# MicroBoard030603.net
KiCad netlist of a schematic drawn in Altium Designer
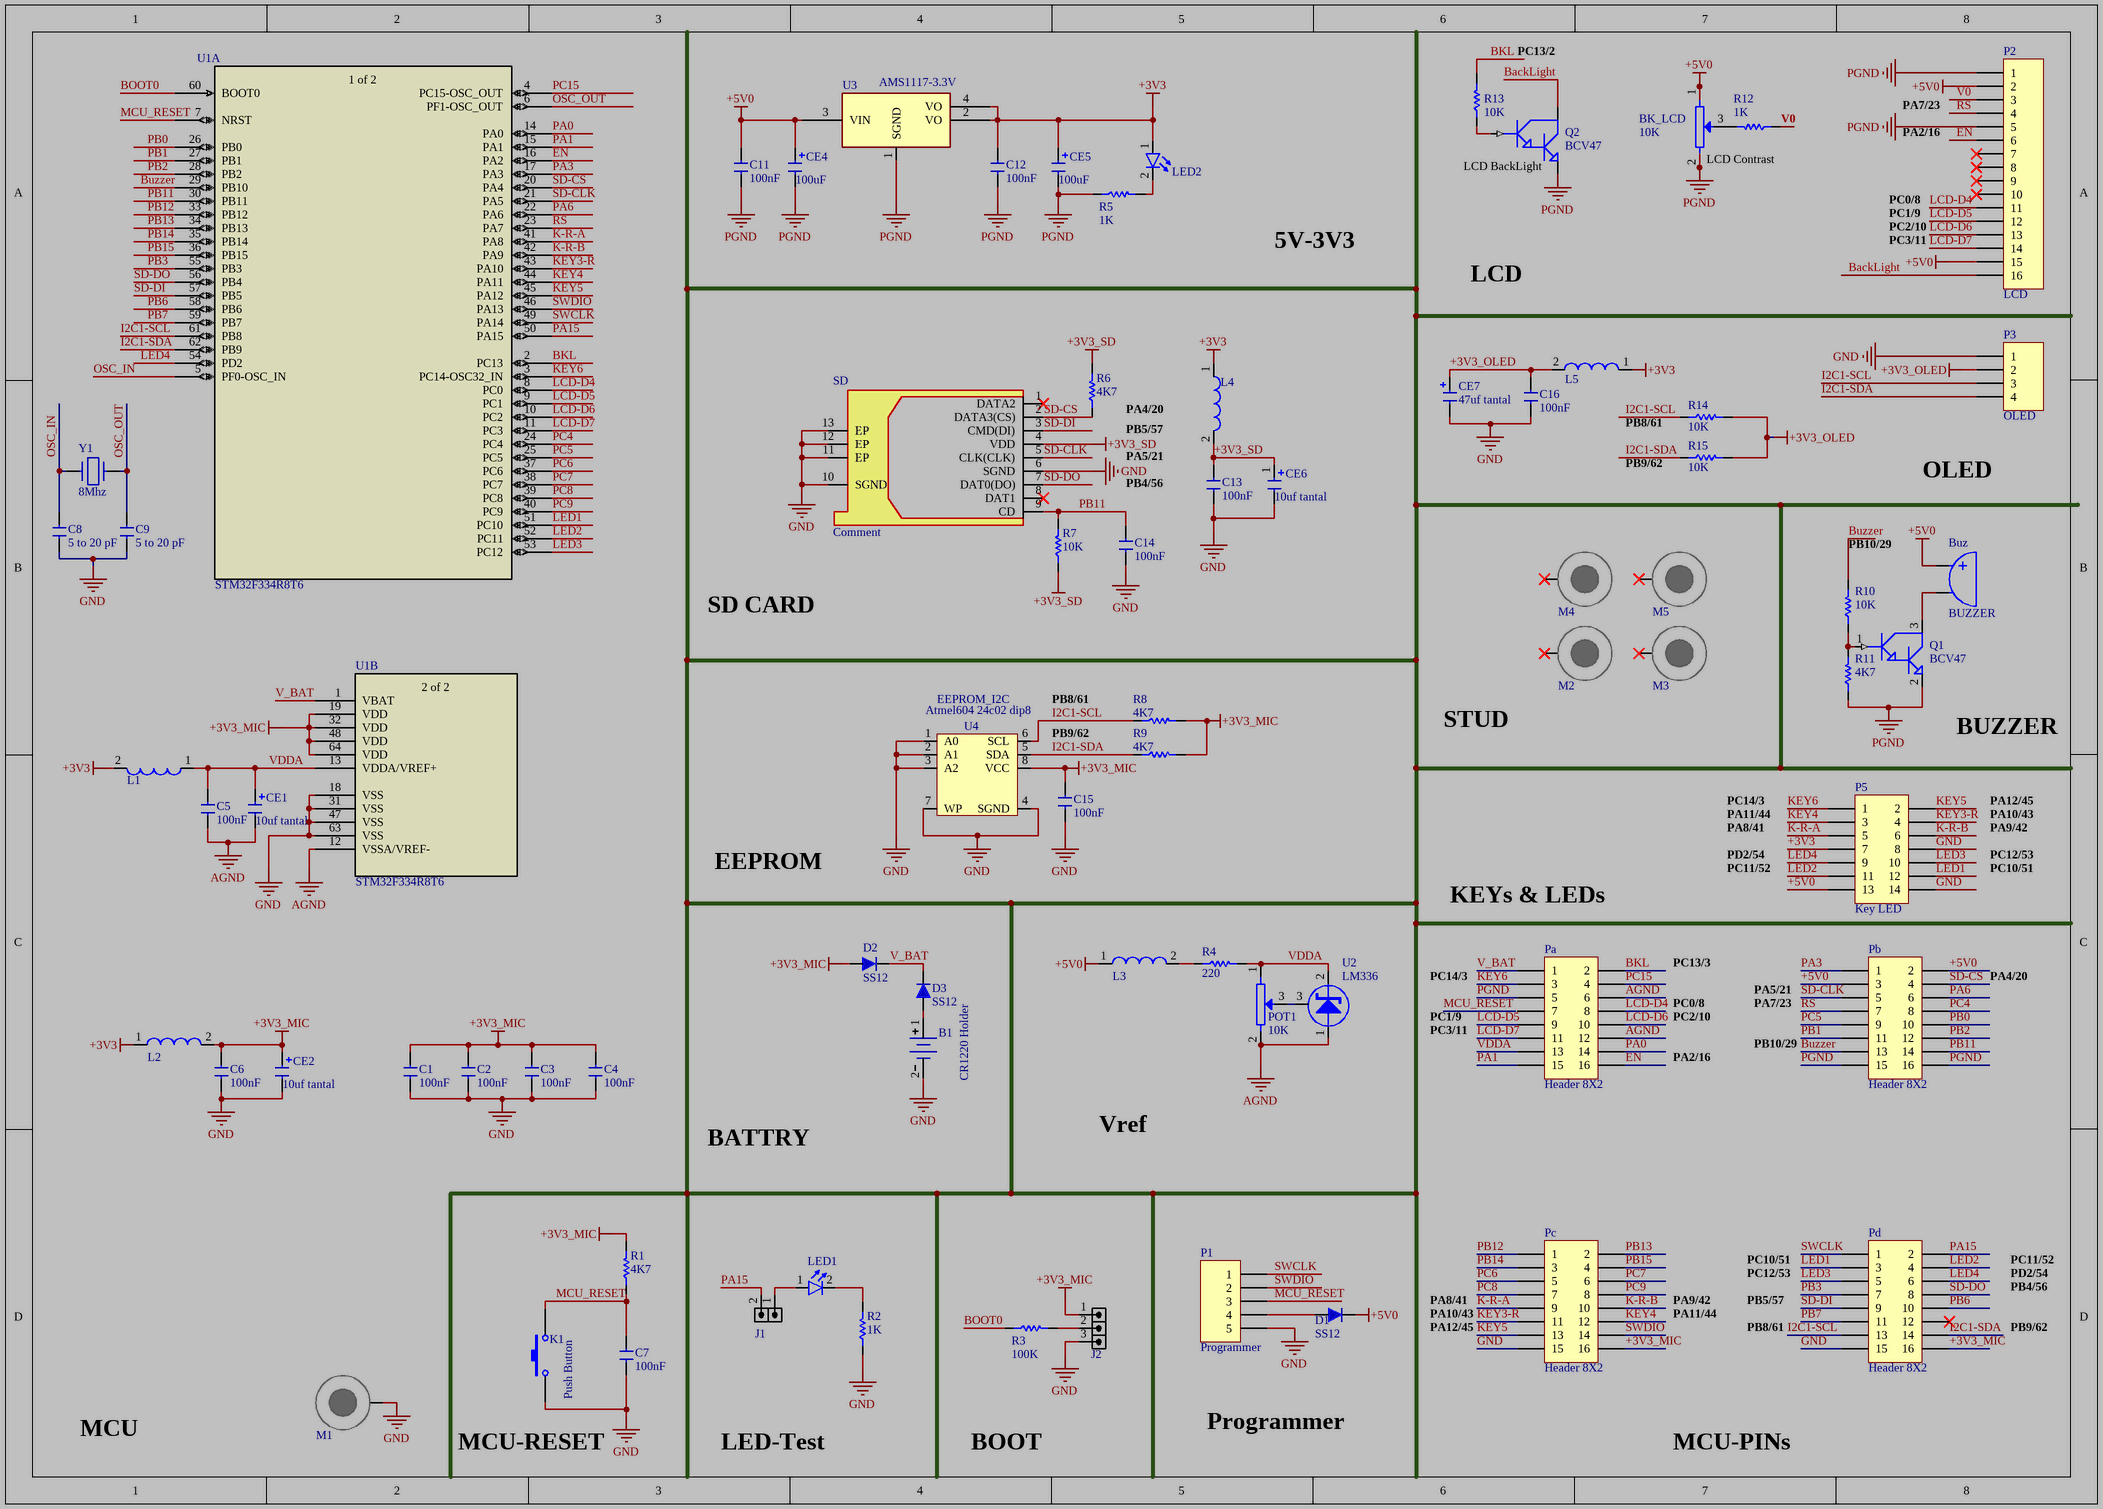
[diagram p0: MicroBoard030603.SchDoc]

(export (version "E")
  (design (tool "Eeschema 10.0.6"))
  (components
    (comp (ref "B1")
      (value "CR1220 Holder")
      (footprint "BAT S")
      (libsource (lib "DotexGroup_LIB") (part "Battry Backup"))
    )
    (comp (ref "BK_LCD")
      (value "10K")
      (footprint "POT-Blue")
      (libsource (lib "1402 Schlib 2020") (part "POT2"))
    )
    (comp (ref "Buz")
      (value "BUZZER")
      (footprint "BUZ")
      (libsource (lib "Previous Backup of Device") (part "BUZZER"))
    )
    (comp (ref "C1")
      (value "Comment")
      (footprint "SMD_CAP_1206.")
      (fields (field (name "ALTIUM_UNNAMED_1") "100nF"))
      (libsource (lib "DotexGroup_LIB") (part "Capacitor SMD"))
    )
    (comp (ref "C2")
      (value "Comment")
      (footprint "SMD_CAP_1206.")
      (fields (field (name "ALTIUM_UNNAMED_1") "100nF"))
      (libsource (lib "DotexGroup_LIB") (part "Capacitor SMD"))
    )
    (comp (ref "C3")
      (value "Comment")
      (footprint "SMD_CAP_1206.")
      (fields (field (name "ALTIUM_UNNAMED_1") "100nF"))
      (libsource (lib "DotexGroup_LIB") (part "Capacitor SMD"))
    )
    (comp (ref "C4")
      (value "Comment")
      (footprint "SMD_CAP_1206.")
      (fields (field (name "ALTIUM_UNNAMED_1") "100nF"))
      (libsource (lib "DotexGroup_LIB") (part "Capacitor SMD"))
    )
    (comp (ref "C5")
      (value "Comment")
      (footprint "SMD_CAP_1206.")
      (fields (field (name "ALTIUM_UNNAMED_1") "100nF"))
      (libsource (lib "DotexGroup_LIB") (part "Capacitor SMD"))
    )
    (comp (ref "C6")
      (value "Comment")
      (footprint "SMD_CAP_1206.")
      (fields (field (name "ALTIUM_UNNAMED_1") "100nF"))
      (libsource (lib "DotexGroup_LIB") (part "Capacitor SMD"))
    )
    (comp (ref "C7")
      (value "Comment")
      (footprint "SMD_CAP_1206.")
      (fields (field (name "ALTIUM_UNNAMED_1") "100nF"))
      (libsource (lib "DotexGroup_LIB") (part "Capacitor SMD"))
    )
    (comp (ref "C8")
      (value "Comment")
      (footprint "CAP 1206 (3216X15L)")
      (fields (field (name "ALTIUM_UNNAMED_1") "5 to 20 pF"))
      (libsource (lib "DotexGroup_LIB") (part "Capacitor SMD"))
    )
    (comp (ref "C9")
      (value "Comment")
      (footprint "CAP 1206 (3216X15L)")
      (fields (field (name "ALTIUM_UNNAMED_1") "5 to 20 pF"))
      (libsource (lib "DotexGroup_LIB") (part "Capacitor SMD"))
    )
    (comp (ref "C11")
      (value "Comment")
      (footprint "SMD_CAP_1206.")
      (fields (field (name "ALTIUM_UNNAMED_1") "100nF"))
      (libsource (lib "DotexGroup_LIB") (part "Capacitor SMD"))
    )
    (comp (ref "C12")
      (value "Comment")
      (footprint "SMD_CAP_1206.")
      (fields (field (name "ALTIUM_UNNAMED_1") "100nF"))
      (libsource (lib "DotexGroup_LIB") (part "Capacitor SMD"))
    )
    (comp (ref "C13")
      (value "Comment")
      (footprint "SMD_CAP_1206.")
      (fields (field (name "ALTIUM_UNNAMED_1") "100nF"))
      (libsource (lib "DotexGroup_LIB") (part "Capacitor SMD"))
    )
    (comp (ref "C14")
      (value "Comment")
      (footprint "SMD_CAP_1206.")
      (fields (field (name "ALTIUM_UNNAMED_1") "100nF"))
      (libsource (lib "DotexGroup_LIB") (part "Capacitor SMD"))
    )
    (comp (ref "C15")
      (value "Comment")
      (footprint "SMD_CAP_1206.")
      (fields (field (name "ALTIUM_UNNAMED_1") "100nF"))
      (libsource (lib "DotexGroup_LIB") (part "Capacitor SMD"))
    )
    (comp (ref "C16")
      (value "Comment")
      (footprint "SMD_CAP_1206.")
      (fields (field (name "ALTIUM_UNNAMED_1") "100nF"))
      (libsource (lib "DotexGroup_LIB") (part "Capacitor SMD"))
    )
    (comp (ref "CE1")
      (value "10uf tantal")
      (footprint "cap-e-2")
      (libsource (lib "DotexGroup_LIB") (part "Capacitor Tantalium"))
    )
    (comp (ref "CE2")
      (value "10uf tantal")
      (footprint "cap-e-2")
      (libsource (lib "DotexGroup_LIB") (part "Capacitor Tantalium"))
    )
    (comp (ref "CE4")
      (value "100uF")
      (footprint "cap-e-4")
      (libsource (lib "DotexGroup_LIB") (part "Capacitor Tantalium"))
    )
    (comp (ref "CE5")
      (value "100uF")
      (footprint "cap-e-4")
      (libsource (lib "DotexGroup_LIB") (part "Capacitor Tantalium"))
    )
    (comp (ref "CE6")
      (value "10uf tantal")
      (footprint "cap-e-2")
      (libsource (lib "") (part "Capacitor Tantalium_1"))
    )
    (comp (ref "CE7")
      (value "47uf tantal")
      (footprint "CAP-E-3")
      (libsource (lib "DotexGroup_LIB") (part "Capacitor Tantalium"))
    )
    (comp (ref "D1")
      (value "SS12")
      (footprint "Diode SMA-M")
      (libsource (lib "DotexGroup_LIB") (part "1N4001"))
    )
    (comp (ref "D2")
      (value "SS12")
      (footprint "Diode SMA-M")
      (libsource (lib "DotexGroup_LIB") (part "1N4001"))
    )
    (comp (ref "D3")
      (value "SS12")
      (footprint "Diode SMA-M")
      (libsource (lib "DotexGroup_LIB") (part "1N4001"))
    )
    (comp (ref "J1")
      (value "HDRM2")
      (footprint "HDR1X2")
      (description "CONN, HEADER, Male, pitch: 2.54mm, 2POS")
      (libsource (lib "conn_header") (part "HDR_M_1X2"))
    )
    (comp (ref "J2")
      (value "HDRM3")
      (footprint "HDR1X3")
      (description "CONN, HEADER, Male, pitch: 2.54mm, 3POS")
      (libsource (lib "conn_header") (part "HDR_M_1X3"))
    )
    (comp (ref "K1")
      (value "Push Button")
      (footprint "SW PB SMD")
      (libsource (lib "DotexGroup_LIB") (part "Push Kay"))
    )
    (comp (ref "L1")
      (value "Comment")
      (footprint "INDC4532")
      (libsource (lib "DotexGroup_LIB") (part "Ferrit Bead"))
    )
    (comp (ref "L2")
      (value "Comment")
      (footprint "L RES")
      (libsource (lib "DotexGroup_LIB") (part "Ferrit Bead"))
    )
    (comp (ref "L3")
      (value "Comment")
      (footprint "L RES")
      (libsource (lib "DotexGroup_LIB") (part "Ferrit Bead"))
    )
    (comp (ref "L4")
      (value "Comment")
      (footprint "L RES")
      (libsource (lib "DotexGroup_LIB") (part "Ferrit Bead"))
    )
    (comp (ref "L5") (value "Comment") (footprint "L RES") (libsource (lib "") (part "Ferrit Bead_1")))
    (comp (ref "LED1")
      (value "HB")
      (footprint "LED_SMD_1206")
      (description "LED")
      (fields (field (name "DESIGNER") "Saeid Jorablo"))
      (libsource (lib "3D") (part "LED"))
    )
    (comp (ref "LED2")
      (value "HB")
      (footprint "LED_SMD_1206")
      (description "LED")
      (fields (field (name "DESIGNER") "Saeid Jorablo"))
      (libsource (lib "3D") (part "LED"))
    )
    (comp (ref "M1")
      (value "Comment")
      (footprint "Stud-hole")
      (description "SCREW mouting, M1.6, 1.6mm diameter and 3.2mm PanHead")
      (libsource (lib "DotexGroup_LIB") (part "SCMH_M1P6"))
    )
    (comp (ref "M2")
      (value "Comment")
      (footprint "Stud-hole")
      (description "SCREW mouting, M1.6, 1.6mm diameter and 3.2mm PanHead")
      (libsource (lib "DotexGroup_LIB") (part "SCMH_M1P6"))
    )
    (comp (ref "M3")
      (value "Comment")
      (footprint "Stud-hole")
      (description "SCREW mouting, M1.6, 1.6mm diameter and 3.2mm PanHead")
      (libsource (lib "DotexGroup_LIB") (part "SCMH_M1P6"))
    )
    (comp (ref "M4")
      (value "Comment")
      (footprint "Stud-hole")
      (description "SCREW mouting, M1.6, 1.6mm diameter and 3.2mm PanHead")
      (libsource (lib "DotexGroup_LIB") (part "SCMH_M1P6"))
    )
    (comp (ref "M5")
      (value "Comment")
      (footprint "Stud-hole")
      (description "SCREW mouting, M1.6, 1.6mm diameter and 3.2mm PanHead")
      (libsource (lib "DotexGroup_LIB") (part "SCMH_M1P6"))
    )
    (comp (ref "P1")
      (value "Programmer")
      (footprint "SIP 5 right")
      (description "Header, 5-Pin")
      (fields (field (name "PUBLISHER") "Altium Limited"))
      (libsource (lib "Miscellaneous Connectors") (part "Header 5"))
    )
    (comp (ref "P2")
      (value "LCD")
      (footprint "HDR1X16")
      (description "Header, 16-Pin")
      (fields (field (name "PUBLISHER") "Altium Limited"))
      (libsource (lib "Miscellaneous Connectors") (part "Header 16"))
    )
    (comp (ref "P3")
      (value "OLED")
      (footprint "sip 4 right")
      (description "Header, 4-Pin")
      (fields (field (name "PUBLISHER") "Altium Limited"))
      (libsource (lib "Miscellaneous Connectors") (part "Header 4"))
    )
    (comp (ref "P5")
      (value "Key LED")
      (footprint "IDC14 r lock")
      (description "Header, 7-Pin, Dual row")
      (fields (field (name "PUBLISHER") "Altium Limited"))
      (libsource (lib "Miscellaneous Connectors") (part "Header 7X2"))
    )
    (comp (ref "Pa")
      (value "Header 8X2")
      (footprint "HDR2X8")
      (description "Header, 8-Pin, Dual row")
      (fields (field (name "PUBLISHER") "Altium Limited"))
      (libsource (lib "Miscellaneous Connectors") (part "Header 8X2"))
    )
    (comp (ref "Pb")
      (value "Header 8X2")
      (footprint "HDR2X8")
      (description "Header, 8-Pin, Dual row")
      (fields (field (name "PUBLISHER") "Altium Limited"))
      (libsource (lib "Miscellaneous Connectors") (part "Header 8X2"))
    )
    (comp (ref "Pc")
      (value "Header 8X2")
      (footprint "HDR2X8")
      (description "Header, 8-Pin, Dual row")
      (fields (field (name "PUBLISHER") "Altium Limited"))
      (libsource (lib "Miscellaneous Connectors") (part "Header 8X2"))
    )
    (comp (ref "Pd")
      (value "Header 8X2")
      (footprint "HDR2X8")
      (description "Header, 8-Pin, Dual row")
      (fields (field (name "PUBLISHER") "Altium Limited"))
      (libsource (lib "Miscellaneous Connectors") (part "Header 8X2"))
    )
    (comp (ref "POT1")
      (value "10K")
      (footprint "pot multi turn")
      (libsource (lib "1402 Schlib 2020") (part "POT2"))
    )
    (comp (ref "Q1") (value "BCV47") (footprint "SOT23_M") (libsource (lib "") (part "NPN DAR_1")))
    (comp (ref "Q2") (value "BCV47") (footprint "SOT23_M") (libsource (lib "MyAltiumLib") (part "NPN DAR")))
    (comp (ref "R1")
      (value "4K7")
      (footprint "RES_1206")
      (description "Resistor")
      (fields (field (name "TOLERANCE") "5%") (field (name "POWER") "1/8 W"))
      (libsource (lib "My Library") (part "Resistor"))
    )
    (comp (ref "R2")
      (value "1K")
      (footprint "RES_1206")
      (description "Resistor")
      (fields (field (name "TOLERANCE") "5%") (field (name "POWER") "1/8 W"))
      (libsource (lib "My Library") (part "Resistor"))
    )
    (comp (ref "R3")
      (value "100K")
      (footprint "RES_1206")
      (description "Resistor")
      (fields (field (name "TOLERANCE") "5%") (field (name "POWER") "1/8 W"))
      (libsource (lib "My Library") (part "Resistor"))
    )
    (comp (ref "R4")
      (value "220")
      (footprint "RES_1206")
      (description "Resistor")
      (fields (field (name "TOLERANCE") "5%") (field (name "POWER") "1/8 W"))
      (libsource (lib "My Library") (part "Resistor"))
    )
    (comp (ref "R5")
      (value "1K")
      (footprint "RES_1206")
      (description "Resistor")
      (fields (field (name "TOLERANCE") "5%") (field (name "POWER") "1/8 W"))
      (libsource (lib "My Library") (part "Resistor"))
    )
    (comp (ref "R6")
      (value "4K7")
      (footprint "RES_1206")
      (description "Resistor")
      (fields (field (name "TOLERANCE") "5%") (field (name "POWER") "1/8 W"))
      (libsource (lib "My Library") (part "Resistor"))
    )
    (comp (ref "R7")
      (value "10K")
      (footprint "RES_1206")
      (description "Resistor")
      (fields (field (name "TOLERANCE") "5%") (field (name "POWER") "1/8 W"))
      (libsource (lib "My Library") (part "Resistor"))
    )
    (comp (ref "R8")
      (value "4K7")
      (footprint "RES_1206")
      (description "Resistor")
      (fields (field (name "TOLERANCE") "5%") (field (name "POWER") "1/8 W"))
      (libsource (lib "My Library") (part "Resistor"))
    )
    (comp (ref "R9")
      (value "4K7")
      (footprint "RES_1206")
      (description "Resistor")
      (fields (field (name "TOLERANCE") "5%") (field (name "POWER") "1/8 W"))
      (libsource (lib "My Library") (part "Resistor"))
    )
    (comp (ref "R10")
      (value "10K")
      (footprint "RES_1206")
      (description "Resistor")
      (fields (field (name "TOLERANCE") "5%") (field (name "POWER") "1/8 W"))
      (libsource (lib "My Library") (part "Resistor"))
    )
    (comp (ref "R11")
      (value "4K7")
      (footprint "RES_1206")
      (description "Resistor")
      (fields (field (name "TOLERANCE") "5%") (field (name "POWER") "1/8 W"))
      (libsource (lib "My Library") (part "Resistor"))
    )
    (comp (ref "R12")
      (value "1K")
      (footprint "RES_1206")
      (description "Resistor")
      (fields (field (name "TOLERANCE") "5%") (field (name "POWER") "1/8 W"))
      (libsource (lib "My Library") (part "Resistor"))
    )
    (comp (ref "R13")
      (value "10K")
      (footprint "RES_1206")
      (description "Resistor")
      (fields (field (name "TOLERANCE") "5%") (field (name "POWER") "1/8 W"))
      (libsource (lib "My Library") (part "Resistor"))
    )
    (comp (ref "R14")
      (value "10K")
      (footprint "RES_1206")
      (description "Resistor")
      (fields (field (name "TOLERANCE") "5%") (field (name "POWER") "1/8 W"))
      (libsource (lib "My Library") (part "Resistor"))
    )
    (comp (ref "R15")
      (value "10K")
      (footprint "RES_1206")
      (description "Resistor")
      (fields (field (name "TOLERANCE") "5%") (field (name "POWER") "1/8 W"))
      (libsource (lib "My Library") (part "Resistor"))
    )
    (comp (ref "SD")
      (value "Comment")
      (footprint "Micro sd csrd")
      (libsource (lib "DotexGroup_LIB") (part "Micro SD Card"))
    )
    (comp (ref "U1")
      (value "STM32F334R8T6")
      (footprint "STM32F334R8T6")
      (description "No Description Available")
      (fields (field (name "COPYRIGHT") "Copyright (C) 2023 Ultra Librarian. All rights reserved."))
      (libsource (lib "STM32F334R8T6") (part "STM32F334R8T6"))
    )
    (comp (ref "U2") (value "LM336") (footprint "LM336") (libsource (lib "MyAltiumLib") (part "LM336")))
    (comp (ref "U3")
      (value "AMS1117-3.3V")
      (footprint "MP04A_M")
      (description "REG, Linear, LDO1V, 0.8A, SOT-223")
      (fields
        (field (name "MANF_P#") "LD1117, LM1117, AMS1117, TLV1117, REG1117, NCP1117, LT1117, SPX1117")
        (field (name "MANF") "TI, ON, ST")
      )
      (libsource (lib "DotexGroup_LIB") (part "VREG_1117_SOT223"))
    )
    (comp (ref "U4")
      (value "EEPROM_I2C")
      (footprint "dip8")
      (libsource (lib "DotexGroup_LIB") (part "AT24C128"))
    )
    (comp (ref "Y1")
      (value "8Mhz")
      (footprint "Crystal SMD")
      (libsource (lib "DotexGroup_LIB") (part "Xtal"))
    )
  )
  (nets
    (net (code "1") (name "+3V3") (class "Default")
      (node (ref "C12") (pin "2") (pintype "passive"))
      (node (ref "CE5") (pin "1") (pintype "passive"))
      (node (ref "L1") (pin "2") (pinfunction "2_2") (pintype "passive"))
      (node (ref "L2") (pin "1") (pinfunction "1_1") (pintype "passive"))
      (node (ref "L4") (pin "1") (pinfunction "1_1") (pintype "passive"))
      (node (ref "L5") (pin "1") (pinfunction "1_1") (pintype "passive"))
      (node (ref "LED2") (pin "1") (pinfunction "A_1") (pintype "passive"))
      (node (ref "P5") (pin "7") (pinfunction "7_7") (pintype "passive"))
      (node (ref "U3") (pin "2") (pinfunction "VO_2") (pintype "passive"))
      (node (ref "U3") (pin "4") (pinfunction "VO_4") (pintype "passive"))
    )
    (net (code "2") (name "+3V3_MIC") (class "Default")
      (node (ref "C1") (pin "2") (pintype "passive"))
      (node (ref "C15") (pin "2") (pintype "passive"))
      (node (ref "C2") (pin "2") (pintype "passive"))
      (node (ref "C3") (pin "2") (pintype "passive"))
      (node (ref "C4") (pin "2") (pintype "passive"))
      (node (ref "C6") (pin "2") (pintype "passive"))
      (node (ref "CE2") (pin "1") (pintype "passive"))
      (node (ref "D2") (pin "1") (pinfunction "A_1") (pintype "passive"))
      (node (ref "J2") (pin "1") (pinfunction "1_1") (pintype "passive"))
      (node (ref "L2") (pin "2") (pinfunction "2_2") (pintype "passive"))
      (node (ref "Pc") (pin "16") (pinfunction "16_16") (pintype "passive"))
      (node (ref "Pd") (pin "16") (pinfunction "16_16") (pintype "passive"))
      (node (ref "R1") (pin "2") (pinfunction "2_2") (pintype "passive"))
      (node (ref "R8") (pin "2") (pinfunction "2_2") (pintype "passive"))
      (node (ref "R9") (pin "2") (pinfunction "2_2") (pintype "passive"))
      (node (ref "U1") (pin "19") (pinfunction "VDD_19") (pintype "power_in"))
      (node (ref "U1") (pin "32") (pinfunction "VDD_32") (pintype "power_in"))
      (node (ref "U1") (pin "48") (pinfunction "VDD_48") (pintype "power_in"))
      (node (ref "U1") (pin "64") (pinfunction "VDD_64") (pintype "power_in"))
      (node (ref "U4") (pin "8") (pinfunction "VCC_8") (pintype "passive"))
    )
    (net (code "3") (name "+3V3_OLED") (class "Default")
      (node (ref "C16") (pin "2") (pintype "passive"))
      (node (ref "CE7") (pin "1") (pintype "passive"))
      (node (ref "L5") (pin "2") (pinfunction "2_2") (pintype "passive"))
      (node (ref "P3") (pin "2") (pinfunction "2_2") (pintype "passive"))
      (node (ref "R14") (pin "2") (pinfunction "2_2") (pintype "passive"))
      (node (ref "R15") (pin "2") (pinfunction "2_2") (pintype "passive"))
    )
    (net (code "4") (name "+3V3_SD") (class "Default")
      (node (ref "C13") (pin "2") (pintype "passive"))
      (node (ref "CE6") (pin "1") (pintype "passive"))
      (node (ref "L4") (pin "2") (pinfunction "2_2") (pintype "passive"))
      (node (ref "R6") (pin "2") (pinfunction "2_2") (pintype "passive"))
      (node (ref "R7") (pin "1") (pinfunction "1_1") (pintype "passive"))
      (node (ref "SD") (pin "4") (pinfunction "VDD_4") (pintype "passive"))
    )
    (net (code "5") (name "+5V0") (class "Default")
      (node (ref "BK_LCD") (pin "1") (pintype "passive"))
      (node (ref "Buz") (pin "1") (pintype "passive"))
      (node (ref "C11") (pin "2") (pintype "passive"))
      (node (ref "CE4") (pin "1") (pintype "passive"))
      (node (ref "D1") (pin "2") (pinfunction "K_2") (pintype "passive"))
      (node (ref "L3") (pin "1") (pinfunction "1_1") (pintype "passive"))
      (node (ref "P2") (pin "15") (pinfunction "15_15") (pintype "passive"))
      (node (ref "P2") (pin "2") (pinfunction "2_2") (pintype "passive"))
      (node (ref "P5") (pin "13") (pinfunction "13_13") (pintype "passive"))
      (node (ref "Pb") (pin "2") (pinfunction "2_2") (pintype "passive"))
      (node (ref "Pb") (pin "3") (pinfunction "3_3") (pintype "passive"))
      (node (ref "U3") (pin "3") (pinfunction "VIN_3") (pintype "passive"))
    )
    (net (code "6") (name "/BKL") (class "Default")
      (node (ref "Pa") (pin "2") (pinfunction "2_2") (pintype "passive"))
      (node (ref "R13") (pin "2") (pinfunction "2_2") (pintype "passive"))
      (node (ref "U1") (pin "2") (pinfunction "PC13_2") (pintype "bidirectional"))
    )
    (net (code "7") (name "/BOOT0") (class "Default")
      (node (ref "R3") (pin "1") (pinfunction "1_1") (pintype "passive"))
      (node (ref "U1") (pin "60") (pinfunction "BOOT0_60") (pintype "input"))
    )
    (net (code "8") (name "/BackLight") (class "Default")
      (node (ref "P2") (pin "16") (pinfunction "16_16") (pintype "passive"))
      (node (ref "Q2") (pin "3") (pinfunction "C_3") (pintype "passive"))
    )
    (net (code "9") (name "/Buzzer") (class "Default")
      (node (ref "Pb") (pin "13") (pinfunction "13_13") (pintype "passive"))
      (node (ref "R10") (pin "2") (pinfunction "2_2") (pintype "passive"))
      (node (ref "U1") (pin "29") (pinfunction "PB10_29") (pintype "bidirectional"))
    )
    (net (code "10") (name "/EN") (class "Default")
      (node (ref "P2") (pin "6") (pinfunction "6_6") (pintype "passive"))
      (node (ref "Pa") (pin "16") (pinfunction "16_16") (pintype "passive"))
      (node (ref "U1") (pin "16") (pinfunction "PA2_16") (pintype "bidirectional"))
    )
    (net (code "11") (name "/I2C1-SCL") (class "Default")
      (node (ref "P3") (pin "3") (pinfunction "3_3") (pintype "passive"))
      (node (ref "Pd") (pin "13") (pinfunction "13_13") (pintype "passive"))
      (node (ref "R14") (pin "1") (pinfunction "1_1") (pintype "passive"))
      (node (ref "R8") (pin "1") (pinfunction "1_1") (pintype "passive"))
      (node (ref "U1") (pin "61") (pinfunction "PB8_61") (pintype "bidirectional"))
      (node (ref "U4") (pin "6") (pinfunction "SCL_6") (pintype "passive"))
    )
    (net (code "12") (name "/I2C1-SDA") (class "Default")
      (node (ref "P3") (pin "4") (pinfunction "4_4") (pintype "passive"))
      (node (ref "Pd") (pin "14") (pinfunction "14_14") (pintype "passive"))
      (node (ref "R15") (pin "1") (pinfunction "1_1") (pintype "passive"))
      (node (ref "R9") (pin "1") (pinfunction "1_1") (pintype "passive"))
      (node (ref "U1") (pin "62") (pinfunction "PB9_62") (pintype "bidirectional"))
      (node (ref "U4") (pin "5") (pinfunction "SDA_5") (pintype "passive"))
    )
    (net (code "13") (name "/K-R-A") (class "Default")
      (node (ref "P5") (pin "5") (pinfunction "5_5") (pintype "passive"))
      (node (ref "Pc") (pin "9") (pinfunction "9_9") (pintype "passive"))
      (node (ref "U1") (pin "41") (pinfunction "PA8_41") (pintype "bidirectional"))
    )
    (net (code "14") (name "/K-R-B") (class "Default")
      (node (ref "P5") (pin "6") (pinfunction "6_6") (pintype "passive"))
      (node (ref "Pc") (pin "10") (pinfunction "10_10") (pintype "passive"))
      (node (ref "U1") (pin "42") (pinfunction "PA9_42") (pintype "bidirectional"))
    )
    (net (code "15") (name "/KEY3-R") (class "Default")
      (node (ref "P5") (pin "4") (pinfunction "4_4") (pintype "passive"))
      (node (ref "Pc") (pin "11") (pinfunction "11_11") (pintype "passive"))
      (node (ref "U1") (pin "43") (pinfunction "PA10_43") (pintype "bidirectional"))
    )
    (net (code "16") (name "/KEY4") (class "Default")
      (node (ref "P5") (pin "3") (pinfunction "3_3") (pintype "passive"))
      (node (ref "Pc") (pin "12") (pinfunction "12_12") (pintype "passive"))
      (node (ref "U1") (pin "44") (pinfunction "PA11_44") (pintype "bidirectional"))
    )
    (net (code "17") (name "/KEY5") (class "Default")
      (node (ref "P5") (pin "2") (pinfunction "2_2") (pintype "passive"))
      (node (ref "Pc") (pin "13") (pinfunction "13_13") (pintype "passive"))
      (node (ref "U1") (pin "45") (pinfunction "PA12_45") (pintype "bidirectional"))
    )
    (net (code "18") (name "/KEY6") (class "Default")
      (node (ref "P5") (pin "1") (pinfunction "1_1") (pintype "passive"))
      (node (ref "Pa") (pin "3") (pinfunction "3_3") (pintype "passive"))
      (node (ref "U1") (pin "3") (pinfunction "PC14-OSC32_IN_3") (pintype "bidirectional"))
    )
    (net (code "19") (name "/LCD-D4") (class "Default")
      (node (ref "P2") (pin "11") (pinfunction "11_11") (pintype "passive"))
      (node (ref "Pa") (pin "8") (pinfunction "8_8") (pintype "passive"))
      (node (ref "U1") (pin "8") (pinfunction "PC0_8") (pintype "bidirectional"))
    )
    (net (code "20") (name "/LCD-D5") (class "Default")
      (node (ref "P2") (pin "12") (pinfunction "12_12") (pintype "passive"))
      (node (ref "Pa") (pin "9") (pinfunction "9_9") (pintype "passive"))
      (node (ref "U1") (pin "9") (pinfunction "PC1_9") (pintype "bidirectional"))
    )
    (net (code "21") (name "/LCD-D6") (class "Default")
      (node (ref "P2") (pin "13") (pinfunction "13_13") (pintype "passive"))
      (node (ref "Pa") (pin "10") (pinfunction "10_10") (pintype "passive"))
      (node (ref "U1") (pin "10") (pinfunction "PC2_10") (pintype "bidirectional"))
    )
    (net (code "22") (name "/LCD-D7") (class "Default")
      (node (ref "P2") (pin "14") (pinfunction "14_14") (pintype "passive"))
      (node (ref "Pa") (pin "11") (pinfunction "11_11") (pintype "passive"))
      (node (ref "U1") (pin "11") (pinfunction "PC3_11") (pintype "bidirectional"))
    )
    (net (code "23") (name "/LED1") (class "Default")
      (node (ref "P5") (pin "12") (pinfunction "12_12") (pintype "passive"))
      (node (ref "Pd") (pin "3") (pinfunction "3_3") (pintype "passive"))
      (node (ref "U1") (pin "51") (pinfunction "PC10_51") (pintype "bidirectional"))
    )
    (net (code "24") (name "/LED2") (class "Default")
      (node (ref "P5") (pin "11") (pinfunction "11_11") (pintype "passive"))
      (node (ref "Pd") (pin "4") (pinfunction "4_4") (pintype "passive"))
      (node (ref "U1") (pin "52") (pinfunction "PC11_52") (pintype "bidirectional"))
    )
    (net (code "25") (name "/LED3") (class "Default")
      (node (ref "P5") (pin "10") (pinfunction "10_10") (pintype "passive"))
      (node (ref "Pd") (pin "5") (pinfunction "5_5") (pintype "passive"))
      (node (ref "U1") (pin "53") (pinfunction "PC12_53") (pintype "bidirectional"))
    )
    (net (code "26") (name "/LED4") (class "Default")
      (node (ref "P5") (pin "9") (pinfunction "9_9") (pintype "passive"))
      (node (ref "Pd") (pin "6") (pinfunction "6_6") (pintype "passive"))
      (node (ref "U1") (pin "54") (pinfunction "PD2_54") (pintype "bidirectional"))
    )
    (net (code "27") (name "/MCU_RESET") (class "Default")
      (node (ref "C7") (pin "1") (pintype "passive"))
      (node (ref "K1") (pin "2") (pinfunction "2_2") (pintype "passive"))
      (node (ref "P1") (pin "3") (pinfunction "3_3") (pintype "passive"))
      (node (ref "R1") (pin "1") (pinfunction "1_1") (pintype "passive"))
      (node (ref "U1") (pin "7") (pinfunction "NRST_7") (pintype "bidirectional"))
    )
    (net (code "28") (name "/OSC_IN") (class "Default")
      (node (ref "C8") (pin "2") (pintype "passive"))
      (node (ref "U1") (pin "5") (pinfunction "PF0-OSC_IN_5") (pintype "bidirectional"))
      (node (ref "Y1") (pin "2") (pintype "passive"))
    )
    (net (code "29") (name "/OSC_OUT") (class "Default")
      (node (ref "C9") (pin "1") (pintype "passive"))
      (node (ref "U1") (pin "6") (pinfunction "PF1-OSC_OUT_6") (pintype "bidirectional"))
      (node (ref "Y1") (pin "1") (pintype "passive"))
    )
    (net (code "30") (name "/PA0") (class "Default")
      (node (ref "Pa") (pin "14") (pinfunction "14_14") (pintype "passive"))
      (node (ref "U1") (pin "14") (pinfunction "PA0_14") (pintype "bidirectional"))
    )
    (net (code "31") (name "/PA1") (class "Default")
      (node (ref "Pa") (pin "15") (pinfunction "15_15") (pintype "passive"))
      (node (ref "U1") (pin "15") (pinfunction "PA1_15") (pintype "bidirectional"))
    )
    (net (code "32") (name "/PA3") (class "Default")
      (node (ref "Pb") (pin "1") (pinfunction "1_1") (pintype "passive"))
      (node (ref "U1") (pin "17") (pinfunction "PA3_17") (pintype "bidirectional"))
    )
    (net (code "33") (name "/PA6") (class "Default")
      (node (ref "Pb") (pin "6") (pinfunction "6_6") (pintype "passive"))
      (node (ref "U1") (pin "22") (pinfunction "PA6_22") (pintype "bidirectional"))
    )
    (net (code "34") (name "/PA15") (class "Default")
      (node (ref "J1") (pin "2") (pinfunction "2_2") (pintype "passive"))
      (node (ref "Pd") (pin "2") (pinfunction "2_2") (pintype "passive"))
      (node (ref "U1") (pin "50") (pinfunction "PA15_50") (pintype "bidirectional"))
    )
    (net (code "35") (name "/PB0") (class "Default")
      (node (ref "Pb") (pin "10") (pinfunction "10_10") (pintype "passive"))
      (node (ref "U1") (pin "26") (pinfunction "PB0_26") (pintype "bidirectional"))
    )
    (net (code "36") (name "/PB1") (class "Default")
      (node (ref "Pb") (pin "11") (pinfunction "11_11") (pintype "passive"))
      (node (ref "U1") (pin "27") (pinfunction "PB1_27") (pintype "bidirectional"))
    )
    (net (code "37") (name "/PB2") (class "Default")
      (node (ref "Pb") (pin "12") (pinfunction "12_12") (pintype "passive"))
      (node (ref "U1") (pin "28") (pinfunction "PB2_28") (pintype "bidirectional"))
    )
    (net (code "38") (name "/PB3") (class "Default")
      (node (ref "Pd") (pin "7") (pinfunction "7_7") (pintype "passive"))
      (node (ref "U1") (pin "55") (pinfunction "PB3_55") (pintype "bidirectional"))
    )
    (net (code "39") (name "/PB6") (class "Default")
      (node (ref "Pd") (pin "10") (pinfunction "10_10") (pintype "passive"))
      (node (ref "U1") (pin "58") (pinfunction "PB6_58") (pintype "bidirectional"))
    )
    (net (code "40") (name "/PB7") (class "Default")
      (node (ref "Pd") (pin "11") (pinfunction "11_11") (pintype "passive"))
      (node (ref "U1") (pin "59") (pinfunction "PB7_59") (pintype "bidirectional"))
    )
    (net (code "41") (name "/PB11") (class "Default")
      (node (ref "C14") (pin "1") (pintype "passive"))
      (node (ref "Pb") (pin "14") (pinfunction "14_14") (pintype "passive"))
      (node (ref "R7") (pin "2") (pinfunction "2_2") (pintype "passive"))
      (node (ref "SD") (pin "9") (pinfunction "CD_9") (pintype "passive"))
      (node (ref "U1") (pin "30") (pinfunction "PB11_30") (pintype "bidirectional"))
    )
    (net (code "42") (name "/PB12") (class "Default")
      (node (ref "Pc") (pin "1") (pinfunction "1_1") (pintype "passive"))
      (node (ref "U1") (pin "33") (pinfunction "PB12_33") (pintype "bidirectional"))
    )
    (net (code "43") (name "/PB13") (class "Default")
      (node (ref "Pc") (pin "2") (pinfunction "2_2") (pintype "passive"))
      (node (ref "U1") (pin "34") (pinfunction "PB13_34") (pintype "bidirectional"))
    )
    (net (code "44") (name "/PB14") (class "Default")
      (node (ref "Pc") (pin "3") (pinfunction "3_3") (pintype "passive"))
      (node (ref "U1") (pin "35") (pinfunction "PB14_35") (pintype "bidirectional"))
    )
    (net (code "45") (name "/PB15") (class "Default")
      (node (ref "Pc") (pin "4") (pinfunction "4_4") (pintype "passive"))
      (node (ref "U1") (pin "36") (pinfunction "PB15_36") (pintype "bidirectional"))
    )
    (net (code "46") (name "/PC4") (class "Default")
      (node (ref "Pb") (pin "8") (pinfunction "8_8") (pintype "passive"))
      (node (ref "U1") (pin "24") (pinfunction "PC4_24") (pintype "bidirectional"))
    )
    (net (code "47") (name "/PC5") (class "Default")
      (node (ref "Pb") (pin "9") (pinfunction "9_9") (pintype "passive"))
      (node (ref "U1") (pin "25") (pinfunction "PC5_25") (pintype "bidirectional"))
    )
    (net (code "48") (name "/PC6") (class "Default")
      (node (ref "Pc") (pin "5") (pinfunction "5_5") (pintype "passive"))
      (node (ref "U1") (pin "37") (pinfunction "PC6_37") (pintype "bidirectional"))
    )
    (net (code "49") (name "/PC7") (class "Default")
      (node (ref "Pc") (pin "6") (pinfunction "6_6") (pintype "passive"))
      (node (ref "U1") (pin "38") (pinfunction "PC7_38") (pintype "bidirectional"))
    )
    (net (code "50") (name "/PC8") (class "Default")
      (node (ref "Pc") (pin "7") (pinfunction "7_7") (pintype "passive"))
      (node (ref "U1") (pin "39") (pinfunction "PC8_39") (pintype "bidirectional"))
    )
    (net (code "51") (name "/PC9") (class "Default")
      (node (ref "Pc") (pin "8") (pinfunction "8_8") (pintype "passive"))
      (node (ref "U1") (pin "40") (pinfunction "PC9_40") (pintype "bidirectional"))
    )
    (net (code "52") (name "/PC15") (class "Default")
      (node (ref "Pa") (pin "4") (pinfunction "4_4") (pintype "passive"))
      (node (ref "U1") (pin "4") (pinfunction "PC15-OSC_OUT_4") (pintype "bidirectional"))
    )
    (net (code "53") (name "/RS") (class "Default")
      (node (ref "P2") (pin "4") (pinfunction "4_4") (pintype "passive"))
      (node (ref "Pb") (pin "7") (pinfunction "7_7") (pintype "passive"))
      (node (ref "U1") (pin "23") (pinfunction "PA7_23") (pintype "bidirectional"))
    )
    (net (code "54") (name "/SD-CLK") (class "Default")
      (node (ref "Pb") (pin "5") (pinfunction "5_5") (pintype "passive"))
      (node (ref "SD") (pin "5") (pinfunction "CLK(CLK)_5") (pintype "passive"))
      (node (ref "U1") (pin "21") (pinfunction "PA5_21") (pintype "bidirectional"))
    )
    (net (code "55") (name "/SD-CS") (class "Default")
      (node (ref "Pb") (pin "4") (pinfunction "4_4") (pintype "passive"))
      (node (ref "R6") (pin "1") (pinfunction "1_1") (pintype "passive"))
      (node (ref "SD") (pin "2") (pinfunction "DATA3(CS)_2") (pintype "passive"))
      (node (ref "U1") (pin "20") (pinfunction "PA4_20") (pintype "bidirectional"))
    )
    (net (code "56") (name "/SD-DI") (class "Default")
      (node (ref "Pd") (pin "9") (pinfunction "9_9") (pintype "passive"))
      (node (ref "SD") (pin "3") (pinfunction "CMD(DI)_3") (pintype "passive"))
      (node (ref "U1") (pin "57") (pinfunction "PB5_57") (pintype "bidirectional"))
    )
    (net (code "57") (name "/SD-DO") (class "Default")
      (node (ref "Pd") (pin "8") (pinfunction "8_8") (pintype "passive"))
      (node (ref "SD") (pin "7") (pinfunction "DAT0(DO)_7") (pintype "passive"))
      (node (ref "U1") (pin "56") (pinfunction "PB4_56") (pintype "bidirectional"))
    )
    (net (code "58") (name "/SWCLK") (class "Default")
      (node (ref "P1") (pin "1") (pinfunction "1_1") (pintype "passive"))
      (node (ref "Pd") (pin "1") (pinfunction "1_1") (pintype "passive"))
      (node (ref "U1") (pin "49") (pinfunction "PA14_49") (pintype "bidirectional"))
    )
    (net (code "59") (name "/SWDIO") (class "Default")
      (node (ref "P1") (pin "2") (pinfunction "2_2") (pintype "passive"))
      (node (ref "Pc") (pin "14") (pinfunction "14_14") (pintype "passive"))
      (node (ref "U1") (pin "46") (pinfunction "PA13_46") (pintype "bidirectional"))
    )
    (net (code "60") (name "/V0") (class "Default")
      (node (ref "P2") (pin "3") (pinfunction "3_3") (pintype "passive"))
      (node (ref "R12") (pin "1") (pinfunction "1_1") (pintype "passive"))
    )
    (net (code "61") (name "/VDDA") (class "Default")
      (node (ref "C5") (pin "2") (pintype "passive"))
      (node (ref "CE1") (pin "1") (pintype "passive"))
      (node (ref "L1") (pin "1") (pinfunction "1_1") (pintype "passive"))
      (node (ref "POT1") (pin "1") (pintype "passive"))
      (node (ref "Pa") (pin "13") (pinfunction "13_13") (pintype "passive"))
      (node (ref "R4") (pin "2") (pinfunction "2_2") (pintype "passive"))
      (node (ref "U1") (pin "13") (pinfunction "VDDA/VREF+_13") (pintype "power_in"))
      (node (ref "U2") (pin "2") (pintype "passive"))
    )
    (net (code "62") (name "/V_BAT") (class "Default")
      (node (ref "D2") (pin "2") (pinfunction "K_2") (pintype "passive"))
      (node (ref "D3") (pin "2") (pinfunction "K_2") (pintype "passive"))
      (node (ref "Pa") (pin "1") (pinfunction "1_1") (pintype "passive"))
      (node (ref "U1") (pin "1") (pinfunction "VBAT_1") (pintype "power_in"))
    )
    (net (code "63") (name "AGND") (class "Default")
      (node (ref "C5") (pin "1") (pintype "passive"))
      (node (ref "CE1") (pin "2") (pintype "passive"))
      (node (ref "POT1") (pin "2") (pintype "passive"))
      (node (ref "Pa") (pin "12") (pinfunction "12_12") (pintype "passive"))
      (node (ref "Pa") (pin "6") (pinfunction "6_6") (pintype "passive"))
      (node (ref "U1") (pin "12") (pinfunction "VSSA/VREF-_12") (pintype "power_in"))
      (node (ref "U2") (pin "1") (pintype "passive"))
    )
    (net (code "64") (name "GND") (class "Default")
      (node (ref "B1") (pin "2") (pinfunction "-_2") (pintype "passive"))
      (node (ref "C1") (pin "1") (pintype "passive"))
      (node (ref "C13") (pin "1") (pintype "passive"))
      (node (ref "C14") (pin "2") (pintype "passive"))
      (node (ref "C15") (pin "1") (pintype "passive"))
      (node (ref "C16") (pin "1") (pintype "passive"))
      (node (ref "C2") (pin "1") (pintype "passive"))
      (node (ref "C3") (pin "1") (pintype "passive"))
      (node (ref "C4") (pin "1") (pintype "passive"))
      (node (ref "C6") (pin "1") (pintype "passive"))
      (node (ref "C7") (pin "2") (pintype "passive"))
      (node (ref "C8") (pin "1") (pintype "passive"))
      (node (ref "C9") (pin "2") (pintype "passive"))
      (node (ref "CE2") (pin "2") (pintype "passive"))
      (node (ref "CE6") (pin "2") (pintype "passive"))
      (node (ref "CE7") (pin "2") (pintype "passive"))
      (node (ref "J2") (pin "3") (pinfunction "3_3") (pintype "passive"))
      (node (ref "K1") (pin "1") (pinfunction "1_1") (pintype "passive"))
      (node (ref "M1") (pin "1") (pinfunction "1_1") (pintype "passive"))
      (node (ref "P1") (pin "5") (pinfunction "5_5") (pintype "passive"))
      (node (ref "P3") (pin "1") (pinfunction "1_1") (pintype "passive"))
      (node (ref "P5") (pin "14") (pinfunction "14_14") (pintype "passive"))
      (node (ref "P5") (pin "8") (pinfunction "8_8") (pintype "passive"))
      (node (ref "Pc") (pin "15") (pinfunction "15_15") (pintype "passive"))
      (node (ref "Pd") (pin "15") (pinfunction "15_15") (pintype "passive"))
      (node (ref "R2") (pin "1") (pinfunction "1_1") (pintype "passive"))
      (node (ref "SD") (pin "10") (pinfunction "SGND_10") (pintype "passive"))
      (node (ref "SD") (pin "11") (pinfunction "EP_11") (pintype "passive"))
      (node (ref "SD") (pin "12") (pinfunction "EP_12") (pintype "passive"))
      (node (ref "SD") (pin "13") (pinfunction "EP_13") (pintype "passive"))
      (node (ref "SD") (pin "6") (pinfunction "SGND_6") (pintype "passive"))
      (node (ref "U1") (pin "18") (pinfunction "VSS_18") (pintype "power_in"))
      (node (ref "U1") (pin "31") (pinfunction "VSS_31") (pintype "power_in"))
      (node (ref "U1") (pin "47") (pinfunction "VSS_47") (pintype "power_in"))
      (node (ref "U1") (pin "63") (pinfunction "VSS_63") (pintype "power_in"))
      (node (ref "U4") (pin "1") (pinfunction "A0_1") (pintype "passive"))
      (node (ref "U4") (pin "2") (pinfunction "A1_2") (pintype "passive"))
      (node (ref "U4") (pin "3") (pinfunction "A2_3") (pintype "passive"))
      (node (ref "U4") (pin "4") (pinfunction "SGND_4") (pintype "passive"))
      (node (ref "U4") (pin "7") (pinfunction "WP_7") (pintype "passive"))
    )
    (net (code "65") (name "Net-(B1-+)") (class "Default")
      (node (ref "B1") (pin "1") (pinfunction "+_1") (pintype "passive"))
      (node (ref "D3") (pin "1") (pinfunction "A_1") (pintype "passive"))
    )
    (net (code "66") (name "Net-(BK_LCD-Pad3)") (class "Default")
      (node (ref "BK_LCD") (pin "3") (pintype "passive"))
      (node (ref "R12") (pin "2") (pinfunction "2_2") (pintype "passive"))
    )
    (net (code "67") (name "Net-(D1-A)") (class "Default")
      (node (ref "D1") (pin "1") (pinfunction "A_1") (pintype "passive"))
      (node (ref "P1") (pin "4") (pinfunction "4_4") (pintype "passive"))
    )
    (net (code "68") (name "Net-(J2-Pad2)") (class "Default")
      (node (ref "J2") (pin "2") (pinfunction "2_2") (pintype "passive"))
      (node (ref "R3") (pin "2") (pinfunction "2_2") (pintype "passive"))
    )
    (net (code "69") (name "Net-(L3-Pad2)") (class "Default")
      (node (ref "L3") (pin "2") (pinfunction "2_2") (pintype "passive"))
      (node (ref "R4") (pin "1") (pinfunction "1_1") (pintype "passive"))
    )
    (net (code "70") (name "Net-(LED1-A)") (class "Default")
      (node (ref "J1") (pin "1") (pinfunction "1_1") (pintype "passive"))
      (node (ref "LED1") (pin "1") (pinfunction "A_1") (pintype "passive"))
    )
    (net (code "71") (name "Net-(LED1-K)") (class "Default")
      (node (ref "LED1") (pin "2") (pinfunction "K_2") (pintype "passive"))
      (node (ref "R2") (pin "2") (pinfunction "2_2") (pintype "passive"))
    )
    (net (code "72") (name "Net-(LED2-K)") (class "Default")
      (node (ref "LED2") (pin "2") (pinfunction "K_2") (pintype "passive"))
      (node (ref "R5") (pin "2") (pinfunction "2_2") (pintype "passive"))
    )
    (net (code "73") (name "Net-(POT1-Pad3)") (class "Default")
      (node (ref "POT1") (pin "3") (pintype "passive"))
      (node (ref "U2") (pin "3") (pintype "passive"))
    )
    (net (code "74") (name "Net-(Q1-B)") (class "Default")
      (node (ref "Q1") (pin "1") (pinfunction "B_1") (pintype "input"))
      (node (ref "R10") (pin "1") (pinfunction "1_1") (pintype "passive"))
      (node (ref "R11") (pin "2") (pinfunction "2_2") (pintype "passive"))
    )
    (net (code "75") (name "Net-(Q1-C)") (class "Default")
      (node (ref "Buz") (pin "2") (pintype "passive"))
      (node (ref "Q1") (pin "3") (pinfunction "C_3") (pintype "passive"))
    )
    (net (code "76") (name "Net-(Q2-B)") (class "Default")
      (node (ref "Q2") (pin "1") (pinfunction "B_1") (pintype "input"))
      (node (ref "R13") (pin "1") (pinfunction "1_1") (pintype "passive"))
    )
    (net (code "77") (name "PGND") (class "Default")
      (node (ref "BK_LCD") (pin "2") (pintype "passive"))
      (node (ref "C11") (pin "1") (pintype "passive"))
      (node (ref "C12") (pin "1") (pintype "passive"))
      (node (ref "CE4") (pin "2") (pintype "passive"))
      (node (ref "CE5") (pin "2") (pintype "passive"))
      (node (ref "P2") (pin "1") (pinfunction "1_1") (pintype "passive"))
      (node (ref "P2") (pin "5") (pinfunction "5_5") (pintype "passive"))
      (node (ref "Pa") (pin "5") (pinfunction "5_5") (pintype "passive"))
      (node (ref "Pb") (pin "15") (pinfunction "15_15") (pintype "passive"))
      (node (ref "Pb") (pin "16") (pinfunction "16_16") (pintype "passive"))
      (node (ref "Q1") (pin "2") (pinfunction "E_2") (pintype "passive"))
      (node (ref "Q2") (pin "2") (pinfunction "E_2") (pintype "passive"))
      (node (ref "R11") (pin "1") (pinfunction "1_1") (pintype "passive"))
      (node (ref "R5") (pin "1") (pinfunction "1_1") (pintype "passive"))
      (node (ref "U3") (pin "1") (pinfunction "SGND_1") (pintype "passive"))
    )
    (net (code "78") (name "unconnected-(M2-Pad1)") (class "Default")
      (node (ref "M2") (pin "1") (pinfunction "1_1") (pintype "passive+no_connect"))
    )
    (net (code "79") (name "unconnected-(M3-Pad1)") (class "Default")
      (node (ref "M3") (pin "1") (pinfunction "1_1") (pintype "passive+no_connect"))
    )
    (net (code "80") (name "unconnected-(M4-Pad1)") (class "Default")
      (node (ref "M4") (pin "1") (pinfunction "1_1") (pintype "passive+no_connect"))
    )
    (net (code "81") (name "unconnected-(M5-Pad1)") (class "Default")
      (node (ref "M5") (pin "1") (pinfunction "1_1") (pintype "passive+no_connect"))
    )
    (net (code "82") (name "unconnected-(P2-Pad7)") (class "Default")
      (node (ref "P2") (pin "7") (pinfunction "7_7") (pintype "passive+no_connect"))
    )
    (net (code "83") (name "unconnected-(P2-Pad8)") (class "Default")
      (node (ref "P2") (pin "8") (pinfunction "8_8") (pintype "passive+no_connect"))
    )
    (net (code "84") (name "unconnected-(P2-Pad9)") (class "Default")
      (node (ref "P2") (pin "9") (pinfunction "9_9") (pintype "passive+no_connect"))
    )
    (net (code "85") (name "unconnected-(P2-Pad10)") (class "Default")
      (node (ref "P2") (pin "10") (pinfunction "10_10") (pintype "passive+no_connect"))
    )
    (net (code "86") (name "unconnected-(Pa-Pad7)") (class "Default")
      (node (ref "Pa") (pin "7") (pinfunction "7_7") (pintype "passive"))
    )
    (net (code "87") (name "unconnected-(Pd-Pad12)") (class "Default")
      (node (ref "Pd") (pin "12") (pinfunction "12_12") (pintype "passive+no_connect"))
    )
    (net (code "88") (name "unconnected-(SD-DAT1-Pad8)") (class "Default")
      (node (ref "SD") (pin "8") (pinfunction "DAT1_8") (pintype "passive+no_connect"))
    )
    (net (code "89") (name "unconnected-(SD-DATA2-Pad1)") (class "Default")
      (node (ref "SD") (pin "1") (pinfunction "DATA2_1") (pintype "passive+no_connect"))
    )
  )
)
